# UserInterface.net
KiCad netlist of a schematic drawn in Altium Designer
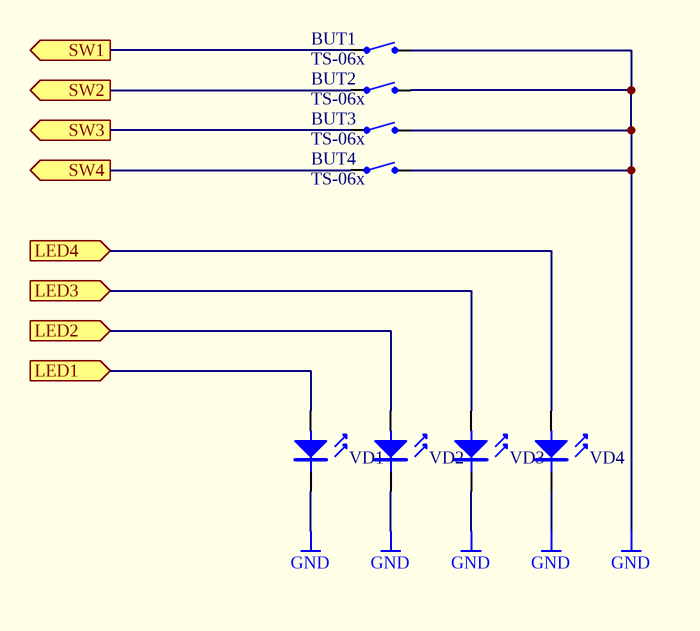
[diagram p0: UserInterface.SchDoc]

(export (version "E")
  (design (tool "Eeschema 10.0.6"))
  (components
    (comp (ref "BUT1")
      (value "TS-06x")
      (footprint "BUT_6x6")
      (description "Tactile push-button")
      (libsource (lib "MainSchlib") (part "SW_TS06"))
    )
    (comp (ref "BUT2")
      (value "TS-06x")
      (footprint "BUT_6x6")
      (description "Tactile push-button")
      (libsource (lib "MainSchlib") (part "SW_TS06"))
    )
    (comp (ref "BUT3")
      (value "TS-06x")
      (footprint "BUT_6x6")
      (description "Tactile push-button")
      (libsource (lib "MainSchlib") (part "SW_TS06"))
    )
    (comp (ref "BUT4")
      (value "TS-06x")
      (footprint "BUT_6x6")
      (description "Tactile push-button")
      (libsource (lib "MainSchlib") (part "SW_TS06"))
    )
    (comp (ref "VD1")
      (value "LED")
      (footprint "LED_3MM")
      (description "LED, 3mm")
      (libsource (lib "MainSchlib") (part "LED"))
    )
    (comp (ref "VD2")
      (value "LED")
      (footprint "LED_3MM")
      (description "LED, 3mm")
      (libsource (lib "MainSchlib") (part "LED"))
    )
    (comp (ref "VD3")
      (value "LED")
      (footprint "LED_3MM")
      (description "LED, 3mm")
      (libsource (lib "MainSchlib") (part "LED"))
    )
    (comp (ref "VD4")
      (value "LED")
      (footprint "LED_3MM")
      (description "LED, 3mm")
      (libsource (lib "MainSchlib") (part "LED"))
    )
  )
  (nets
    (net (code "1") (name "/LED1") (class "Default")
      (node (ref "VD1") (pin "1") (pinfunction "A1_1") (pintype "passive"))
    )
    (net (code "2") (name "/LED2") (class "Default")
      (node (ref "VD2") (pin "1") (pinfunction "A1_1") (pintype "passive"))
    )
    (net (code "3") (name "/LED3") (class "Default")
      (node (ref "VD3") (pin "1") (pinfunction "A1_1") (pintype "passive"))
    )
    (net (code "4") (name "/LED4") (class "Default")
      (node (ref "VD4") (pin "1") (pinfunction "A1_1") (pintype "passive"))
    )
    (net (code "5") (name "/SW1") (class "Default")
      (node (ref "BUT1") (pin "2") (pinfunction "2_2") (pintype "passive"))
    )
    (net (code "6") (name "/SW2") (class "Default")
      (node (ref "BUT2") (pin "2") (pinfunction "2_2") (pintype "passive"))
    )
    (net (code "7") (name "/SW3") (class "Default")
      (node (ref "BUT3") (pin "2") (pinfunction "2_2") (pintype "passive"))
    )
    (net (code "8") (name "/SW4") (class "Default")
      (node (ref "BUT4") (pin "2") (pinfunction "2_2") (pintype "passive"))
    )
    (net (code "9") (name "GND") (class "Default")
      (node (ref "BUT1") (pin "1") (pinfunction "1_1") (pintype "passive"))
      (node (ref "BUT2") (pin "1") (pinfunction "1_1") (pintype "passive"))
      (node (ref "BUT3") (pin "1") (pinfunction "1_1") (pintype "passive"))
      (node (ref "BUT4") (pin "1") (pinfunction "1_1") (pintype "passive"))
      (node (ref "VD1") (pin "2") (pinfunction "K_2") (pintype "passive"))
      (node (ref "VD2") (pin "2") (pinfunction "K_2") (pintype "passive"))
      (node (ref "VD3") (pin "2") (pinfunction "K_2") (pintype "passive"))
      (node (ref "VD4") (pin "2") (pinfunction "K_2") (pintype "passive"))
    )
  )
)
